# Voltage_regulator.net
KiCad netlist of a schematic drawn in Altium Designer
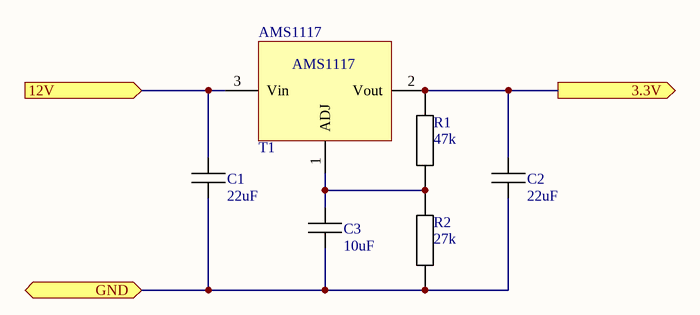
[diagram p0: Voltage regulator.SchDoc]

(export (version "E")
  (design (tool "Eeschema 10.0.6"))
  (components
    (comp (ref "AMS1117") (value "T1") (libsource (lib "AMS1117 breakout") (part "AMS1117")))
    (comp (ref "C1")
      (value "22uF")
      (footprint "0805-C")
      (libsource (lib "AMS1117 breakout") (part "Capacitor"))
    )
    (comp (ref "C2")
      (value "22uF")
      (footprint "0805-C")
      (libsource (lib "AMS1117 breakout") (part "Capacitor"))
    )
    (comp (ref "C3")
      (value "10uF")
      (footprint "0805-C")
      (libsource (lib "AMS1117 breakout") (part "Capacitor"))
    )
    (comp (ref "R1")
      (value "47k")
      (footprint "0805-R")
      (libsource (lib "AMS1117 breakout") (part "Resistor"))
    )
    (comp (ref "R2")
      (value "27k")
      (footprint "0805-R")
      (libsource (lib "AMS1117 breakout") (part "Resistor"))
    )
  )
  (nets
    (net (code "1") (name "/3.3V") (class "Default")
      (node (ref "AMS1117") (pin "2") (pinfunction "Vout_2") (pintype "passive"))
      (node (ref "C2") (pin "2") (pinfunction "2_2") (pintype "passive"))
      (node (ref "R1") (pin "2") (pinfunction "2_2") (pintype "passive"))
    )
    (net (code "2") (name "/12V") (class "Default")
      (node (ref "AMS1117") (pin "3") (pinfunction "Vin_3") (pintype "passive"))
      (node (ref "C1") (pin "2") (pinfunction "2_2") (pintype "passive"))
    )
    (net (code "3") (name "/GND") (class "Default")
      (node (ref "C1") (pin "1") (pinfunction "1_1") (pintype "passive"))
      (node (ref "C2") (pin "1") (pinfunction "1_1") (pintype "passive"))
      (node (ref "C3") (pin "1") (pinfunction "1_1") (pintype "passive"))
      (node (ref "R2") (pin "1") (pinfunction "1_1") (pintype "passive"))
    )
    (net (code "4") (name "Net-(AMS1117-ADJ)") (class "Default")
      (node (ref "AMS1117") (pin "1") (pinfunction "ADJ_1") (pintype "passive"))
      (node (ref "C3") (pin "2") (pinfunction "2_2") (pintype "passive"))
      (node (ref "R1") (pin "1") (pinfunction "1_1") (pintype "passive"))
      (node (ref "R2") (pin "2") (pinfunction "2_2") (pintype "passive"))
    )
  )
)
